# uhf_indication_v2.net
KiCad netlist of a schematic drawn in EAGLE
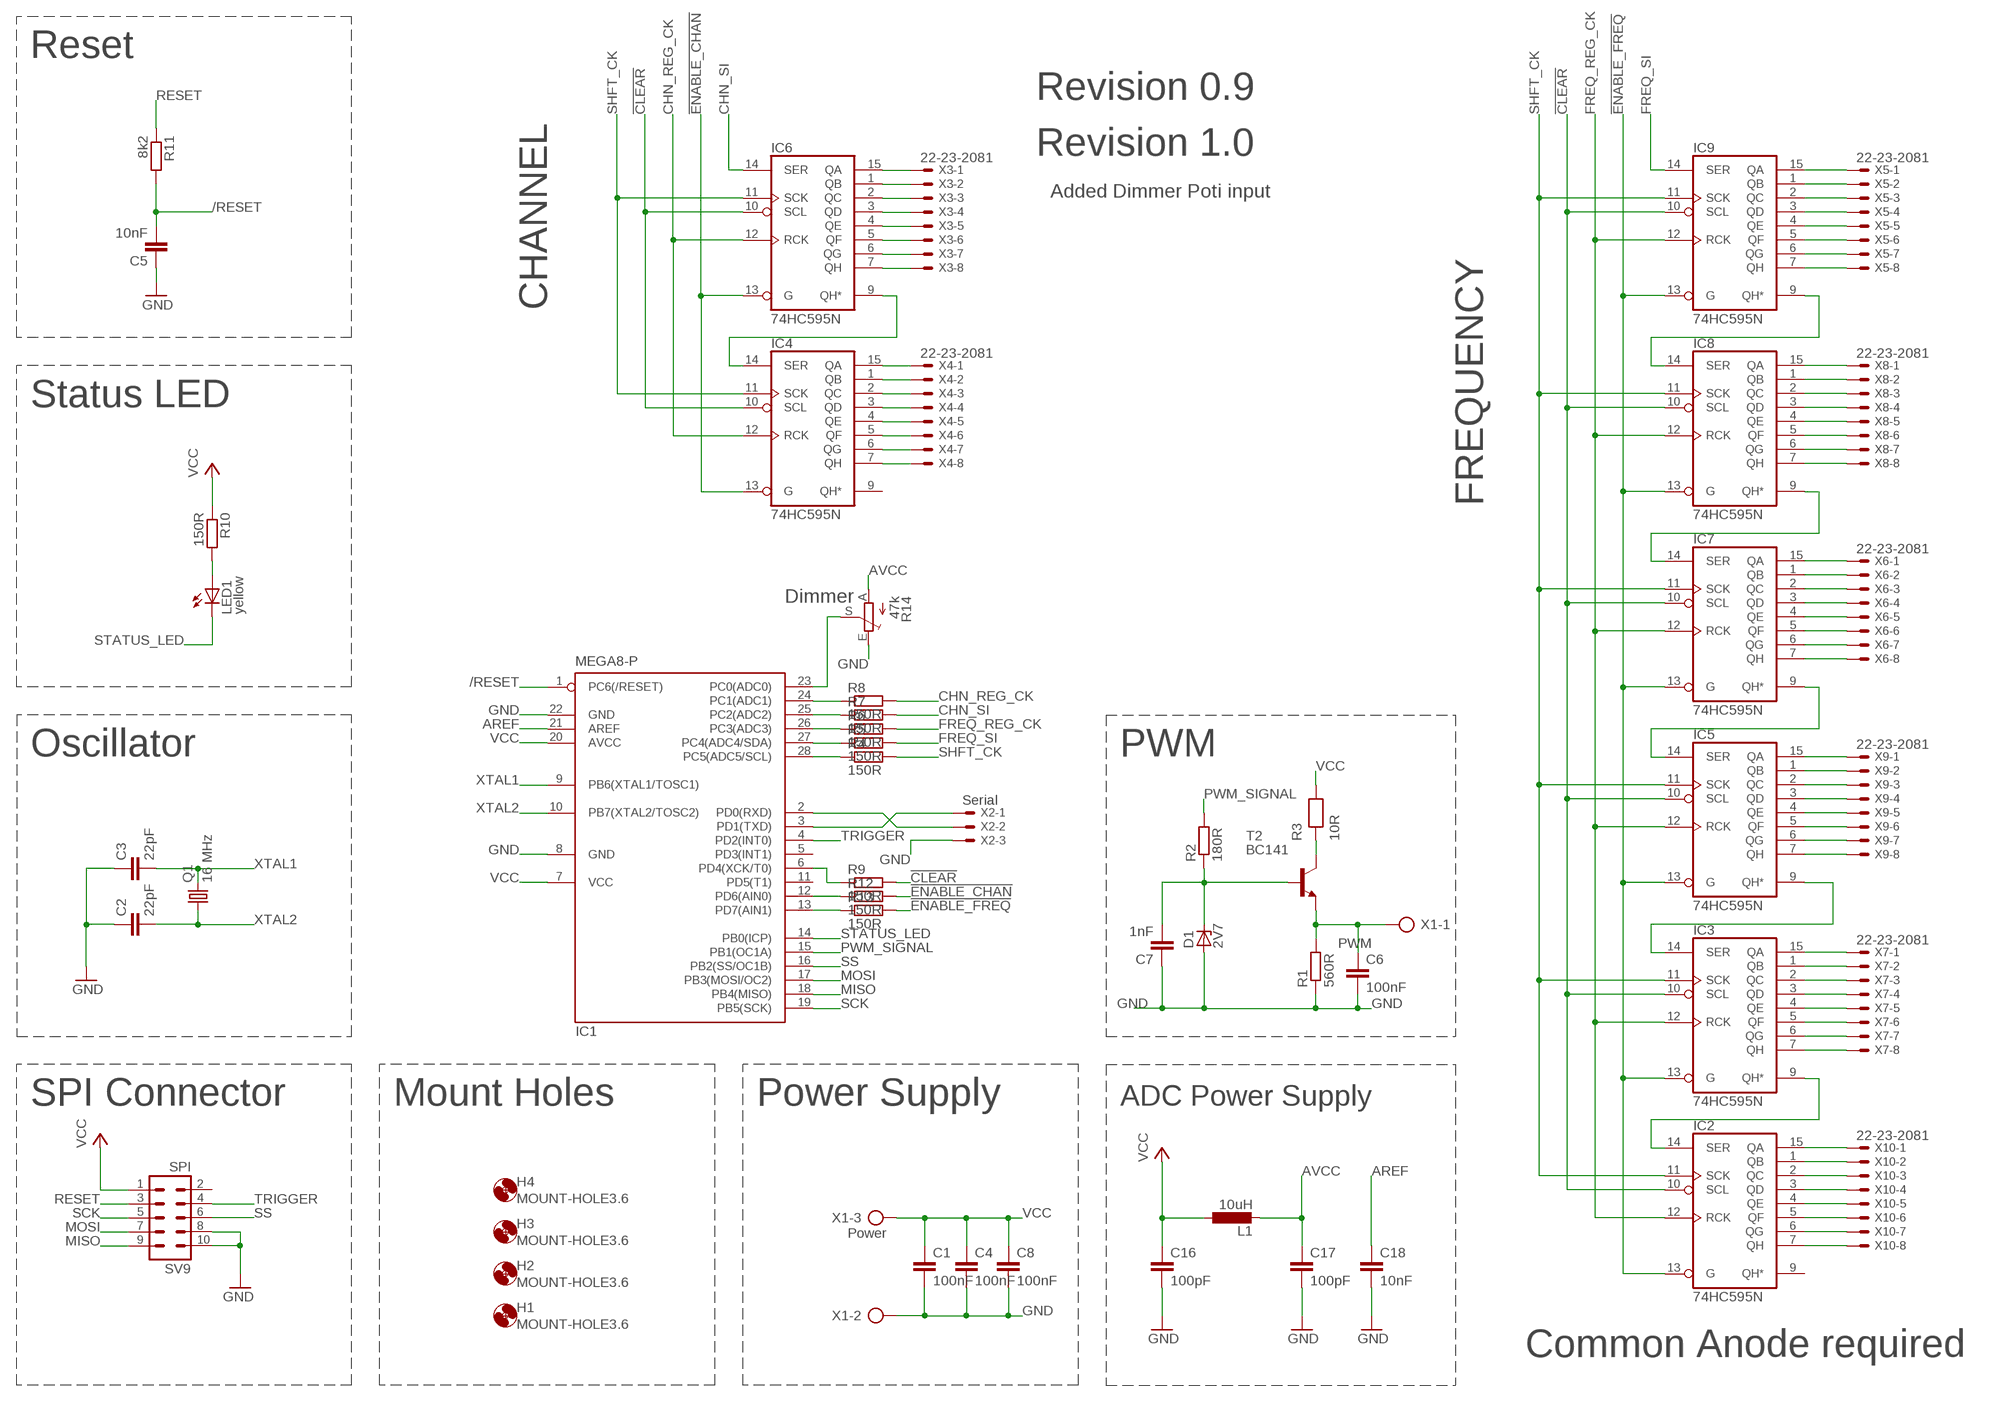
[diagram p0: schematic, sheet 1]

(export (version "E")
  (design (tool "Eeschema 10.0.6"))
  (components
    (comp (ref "C1")
      (value "100nF")
      (footprint "eagle-import:C050-024X044")
      (libsource (lib "eagle-import") (part "C-EU050-024X044"))
    )
    (comp (ref "C2")
      (value "22pF")
      (footprint "eagle-import:C025-025X050")
      (libsource (lib "eagle-import") (part "C-EU025-025X050"))
    )
    (comp (ref "C3")
      (value "22pF")
      (footprint "eagle-import:C025-025X050")
      (libsource (lib "eagle-import") (part "C-EU025-025X050"))
    )
    (comp (ref "C4")
      (value "100nF")
      (footprint "eagle-import:C050-024X044")
      (libsource (lib "eagle-import") (part "C-EU050-024X044"))
    )
    (comp (ref "C5")
      (value "10nF")
      (footprint "eagle-import:C025-025X050")
      (libsource (lib "eagle-import") (part "C-EU025-025X050"))
    )
    (comp (ref "C6")
      (value "100nF")
      (footprint "eagle-import:C050-024X044")
      (libsource (lib "eagle-import") (part "C-EU050-024X044"))
    )
    (comp (ref "C7")
      (value "1nF")
      (footprint "eagle-import:C025-025X050")
      (libsource (lib "eagle-import") (part "C-EU025-025X050"))
    )
    (comp (ref "C8")
      (value "100nF")
      (footprint "eagle-import:C050-024X044")
      (libsource (lib "eagle-import") (part "C-EU050-024X044"))
    )
    (comp (ref "C16")
      (value "100pF")
      (footprint "eagle-import:C025-025X050")
      (libsource (lib "eagle-import") (part "C-EU025-025X050"))
    )
    (comp (ref "C17")
      (value "100pF")
      (footprint "eagle-import:C025-025X050")
      (libsource (lib "eagle-import") (part "C-EU025-025X050"))
    )
    (comp (ref "C18")
      (value "10nF")
      (footprint "eagle-import:C025-025X050")
      (libsource (lib "eagle-import") (part "C-EU025-025X050"))
    )
    (comp (ref "D1")
      (value "2V7")
      (footprint "eagle-import:ZDIO-10")
      (libsource (lib "eagle-import") (part "ZENER-DIODEZD-10"))
    )
    (comp (ref "H1")
      (value "MOUNT-HOLE3.6")
      (footprint "eagle-import:3,6")
      (libsource (lib "eagle-import") (part "MOUNT-HOLE3.6"))
    )
    (comp (ref "H2")
      (value "MOUNT-HOLE3.6")
      (footprint "eagle-import:3,6")
      (libsource (lib "eagle-import") (part "MOUNT-HOLE3.6"))
    )
    (comp (ref "H3")
      (value "MOUNT-HOLE3.6")
      (footprint "eagle-import:3,6")
      (libsource (lib "eagle-import") (part "MOUNT-HOLE3.6"))
    )
    (comp (ref "H4")
      (value "MOUNT-HOLE3.6")
      (footprint "eagle-import:3,6")
      (libsource (lib "eagle-import") (part "MOUNT-HOLE3.6"))
    )
    (comp (ref "IC1")
      (value "MEGA8-P")
      (footprint "eagle-import:DIL28-3")
      (libsource (lib "eagle-import") (part "MEGA8-P"))
    )
    (comp (ref "IC2")
      (value "74HC595N")
      (footprint "eagle-import:DIL16")
      (libsource (lib "eagle-import") (part "74595NHC"))
    )
    (comp (ref "IC3")
      (value "74HC595N")
      (footprint "eagle-import:DIL16")
      (libsource (lib "eagle-import") (part "74595NHC"))
    )
    (comp (ref "IC4")
      (value "74HC595N")
      (footprint "eagle-import:DIL16")
      (libsource (lib "eagle-import") (part "74595NHC"))
    )
    (comp (ref "IC5")
      (value "74HC595N")
      (footprint "eagle-import:DIL16")
      (libsource (lib "eagle-import") (part "74595NHC"))
    )
    (comp (ref "IC6")
      (value "74HC595N")
      (footprint "eagle-import:DIL16")
      (libsource (lib "eagle-import") (part "74595NHC"))
    )
    (comp (ref "IC7")
      (value "74HC595N")
      (footprint "eagle-import:DIL16")
      (libsource (lib "eagle-import") (part "74595NHC"))
    )
    (comp (ref "IC8")
      (value "74HC595N")
      (footprint "eagle-import:DIL16")
      (libsource (lib "eagle-import") (part "74595NHC"))
    )
    (comp (ref "IC9")
      (value "74HC595N")
      (footprint "eagle-import:DIL16")
      (libsource (lib "eagle-import") (part "74595NHC"))
    )
    (comp (ref "L1")
      (value "10uH")
      (footprint "eagle-import:2200-15.24")
      (libsource (lib "eagle-import") (part "L-EU2200-15.24"))
    )
    (comp (ref "LED1")
      (value "yellow")
      (footprint "eagle-import:CHIPLED_1206")
      (libsource (lib "eagle-import") (part "LEDCHIPLED_1206"))
    )
    (comp (ref "Q1")
      (value "16 MHz")
      (footprint "eagle-import:HC18U-V")
      (libsource (lib "eagle-import") (part "CRYSTALHC18U-V"))
    )
    (comp (ref "R1")
      (value "560R")
      (footprint "eagle-import:0207_2V@1")
      (libsource (lib "eagle-import") (part "R-EU_0207/2V"))
    )
    (comp (ref "R2")
      (value "180R")
      (footprint "eagle-import:0207_2V@1")
      (libsource (lib "eagle-import") (part "R-EU_0207/2V"))
    )
    (comp (ref "R3")
      (value "10R")
      (footprint "eagle-import:208-08")
      (libsource (lib "eagle-import") (part "RESISTOR"))
    )
    (comp (ref "R4")
      (value "150R")
      (footprint "eagle-import:R0805")
      (libsource (lib "eagle-import") (part "R-EU_R0805"))
    )
    (comp (ref "R5")
      (value "150R")
      (footprint "eagle-import:R0805")
      (libsource (lib "eagle-import") (part "R-EU_R0805"))
    )
    (comp (ref "R6")
      (value "150R")
      (footprint "eagle-import:R0805")
      (libsource (lib "eagle-import") (part "R-EU_R0805"))
    )
    (comp (ref "R7")
      (value "150R")
      (footprint "eagle-import:R0805")
      (libsource (lib "eagle-import") (part "R-EU_R0805"))
    )
    (comp (ref "R8")
      (value "150R")
      (footprint "eagle-import:R0805")
      (libsource (lib "eagle-import") (part "R-EU_R0805"))
    )
    (comp (ref "R9")
      (value "150R")
      (footprint "eagle-import:R0805")
      (libsource (lib "eagle-import") (part "R-EU_R0805"))
    )
    (comp (ref "R10")
      (value "150R")
      (footprint "eagle-import:R0805")
      (libsource (lib "eagle-import") (part "R-EU_R0805"))
    )
    (comp (ref "R11")
      (value "8k2")
      (footprint "eagle-import:M0805")
      (libsource (lib "eagle-import") (part "R-EU_M0805"))
    )
    (comp (ref "R12")
      (value "150R")
      (footprint "eagle-import:R0805")
      (libsource (lib "eagle-import") (part "R-EU_R0805"))
    )
    (comp (ref "R13")
      (value "150R")
      (footprint "eagle-import:R0805")
      (libsource (lib "eagle-import") (part "R-EU_R0805"))
    )
    (comp (ref "R14")
      (value "47k")
      (footprint "eagle-import:B25V")
      (libsource (lib "eagle-import") (part "TRIM_EU-B25V"))
    )
    (comp (ref "SV9")
      (value "SPI")
      (footprint "eagle-import:ML10")
      (libsource (lib "eagle-import") (part "ML10"))
    )
    (comp (ref "T2")
      (value "BC141")
      (footprint "eagle-import:TO39")
      (libsource (lib "eagle-import") (part "-NPN-TO39-EBCBC141-16"))
    )
    (comp (ref "X1")
      (value "Power")
      (footprint "eagle-import:AK500_3")
      (libsource (lib "eagle-import") (part "AK500/3"))
    )
    (comp (ref "X2")
      (value "Serial")
      (footprint "eagle-import:22-23-2031")
      (libsource (lib "eagle-import") (part "22-23-2031"))
    )
    (comp (ref "X3")
      (value "22-23-2081")
      (footprint "eagle-import:22-23-2081")
      (libsource (lib "eagle-import") (part "22-23-2081"))
    )
    (comp (ref "X4")
      (value "22-23-2081")
      (footprint "eagle-import:22-23-2081")
      (libsource (lib "eagle-import") (part "22-23-2081"))
    )
    (comp (ref "X5")
      (value "22-23-2081")
      (footprint "eagle-import:22-23-2081")
      (libsource (lib "eagle-import") (part "22-23-2081"))
    )
    (comp (ref "X6")
      (value "22-23-2081")
      (footprint "eagle-import:22-23-2081")
      (libsource (lib "eagle-import") (part "22-23-2081"))
    )
    (comp (ref "X7")
      (value "22-23-2081")
      (footprint "eagle-import:22-23-2081")
      (libsource (lib "eagle-import") (part "22-23-2081"))
    )
    (comp (ref "X8")
      (value "22-23-2081")
      (footprint "eagle-import:22-23-2081")
      (libsource (lib "eagle-import") (part "22-23-2081"))
    )
    (comp (ref "X9")
      (value "22-23-2081")
      (footprint "eagle-import:22-23-2081")
      (libsource (lib "eagle-import") (part "22-23-2081"))
    )
    (comp (ref "X10")
      (value "22-23-2081")
      (footprint "eagle-import:22-23-2081")
      (libsource (lib "eagle-import") (part "22-23-2081"))
    )
  )
  (nets
    (net (code "1") (name "/AREF") (class "Default")
      (node (ref "C18") (pin "1") (pinfunction "1_1") (pintype "passive"))
      (node (ref "IC1") (pin "21") (pinfunction "AREF_21") (pintype "passive"))
    )
    (net (code "2") (name "/AVCC") (class "Default")
      (node (ref "C17") (pin "1") (pinfunction "1_1") (pintype "passive"))
      (node (ref "L1") (pin "2") (pinfunction "2_2") (pintype "passive"))
      (node (ref "R14") (pin "A") (pinfunction "A_A") (pintype "passive"))
    )
    (net (code "3") (name "/CHN_REG_CK") (class "Default")
      (node (ref "IC4") (pin "12") (pinfunction "RCK_12") (pintype "input"))
      (node (ref "IC6") (pin "12") (pinfunction "RCK_12") (pintype "input"))
      (node (ref "R8") (pin "2") (pinfunction "2_2") (pintype "passive"))
    )
    (net (code "4") (name "/CHN_SI") (class "Default")
      (node (ref "IC6") (pin "14") (pinfunction "SER_14") (pintype "input"))
      (node (ref "R7") (pin "2") (pinfunction "2_2") (pintype "passive"))
    )
    (net (code "5") (name "/FREQ_REG_CK") (class "Default")
      (node (ref "IC2") (pin "12") (pinfunction "RCK_12") (pintype "input"))
      (node (ref "IC3") (pin "12") (pinfunction "RCK_12") (pintype "input"))
      (node (ref "IC5") (pin "12") (pinfunction "RCK_12") (pintype "input"))
      (node (ref "IC7") (pin "12") (pinfunction "RCK_12") (pintype "input"))
      (node (ref "IC8") (pin "12") (pinfunction "RCK_12") (pintype "input"))
      (node (ref "IC9") (pin "12") (pinfunction "RCK_12") (pintype "input"))
      (node (ref "R6") (pin "2") (pinfunction "2_2") (pintype "passive"))
    )
    (net (code "6") (name "/FREQ_SI") (class "Default")
      (node (ref "IC9") (pin "14") (pinfunction "SER_14") (pintype "input"))
      (node (ref "R5") (pin "2") (pinfunction "2_2") (pintype "passive"))
    )
    (net (code "7") (name "/MISO") (class "Default")
      (node (ref "IC1") (pin "18") (pinfunction "PB4(MISO)_18") (pintype "bidirectional"))
      (node (ref "SV9") (pin "9") (pinfunction "9_9") (pintype "passive"))
    )
    (net (code "8") (name "/MOSI") (class "Default")
      (node (ref "IC1") (pin "17") (pinfunction "PB3(MOSI/OC2)_17") (pintype "bidirectional"))
      (node (ref "SV9") (pin "7") (pinfunction "7_7") (pintype "passive"))
    )
    (net (code "9") (name "/PWM") (class "Default")
      (node (ref "C6") (pin "1") (pinfunction "1_1") (pintype "passive"))
      (node (ref "R1") (pin "2") (pinfunction "2_2") (pintype "passive"))
      (node (ref "T2") (pin "1") (pinfunction "E_1") (pintype "passive"))
      (node (ref "X1") (pin "1") (pinfunction "KL_1") (pintype "passive"))
    )
    (net (code "10") (name "/PWM_SIGNAL") (class "Default")
      (node (ref "IC1") (pin "15") (pinfunction "PB1(OC1A)_15") (pintype "bidirectional"))
      (node (ref "R2") (pin "2") (pinfunction "2_2") (pintype "passive"))
    )
    (net (code "11") (name "/RESET") (class "Default")
      (node (ref "R11") (pin "1") (pinfunction "1_1") (pintype "passive"))
      (node (ref "SV9") (pin "3") (pinfunction "3_3") (pintype "passive"))
    )
    (net (code "12") (name "/SCK") (class "Default")
      (node (ref "IC1") (pin "19") (pinfunction "PB5(SCK)_19") (pintype "bidirectional"))
      (node (ref "SV9") (pin "5") (pinfunction "5_5") (pintype "passive"))
    )
    (net (code "13") (name "/SHFT_CK") (class "Default")
      (node (ref "IC2") (pin "11") (pinfunction "SCK_11") (pintype "input"))
      (node (ref "IC3") (pin "11") (pinfunction "SCK_11") (pintype "input"))
      (node (ref "IC4") (pin "11") (pinfunction "SCK_11") (pintype "input"))
      (node (ref "IC5") (pin "11") (pinfunction "SCK_11") (pintype "input"))
      (node (ref "IC6") (pin "11") (pinfunction "SCK_11") (pintype "input"))
      (node (ref "IC7") (pin "11") (pinfunction "SCK_11") (pintype "input"))
      (node (ref "IC8") (pin "11") (pinfunction "SCK_11") (pintype "input"))
      (node (ref "IC9") (pin "11") (pinfunction "SCK_11") (pintype "input"))
      (node (ref "R4") (pin "2") (pinfunction "2_2") (pintype "passive"))
    )
    (net (code "14") (name "/SS") (class "Default")
      (node (ref "IC1") (pin "16") (pinfunction "PB2(SS/OC1B)_16") (pintype "bidirectional"))
      (node (ref "SV9") (pin "6") (pinfunction "6_6") (pintype "passive"))
    )
    (net (code "15") (name "/STATUS_LED") (class "Default")
      (node (ref "IC1") (pin "14") (pinfunction "PB0(ICP)_14") (pintype "bidirectional"))
      (node (ref "LED1") (pin "C") (pinfunction "C_C") (pintype "passive"))
    )
    (net (code "16") (name "/TRIGGER") (class "Default")
      (node (ref "IC1") (pin "4") (pinfunction "PD2(INT0)_4") (pintype "bidirectional"))
      (node (ref "SV9") (pin "4") (pinfunction "4_4") (pintype "passive"))
    )
    (net (code "17") (name "/XTAL1") (class "Default")
      (node (ref "C3") (pin "2") (pinfunction "2_2") (pintype "passive"))
      (node (ref "IC1") (pin "9") (pinfunction "PB6(XTAL1/TOSC1)_9") (pintype "bidirectional"))
      (node (ref "Q1") (pin "2") (pinfunction "2_2") (pintype "passive"))
    )
    (net (code "18") (name "/XTAL2") (class "Default")
      (node (ref "C2") (pin "2") (pinfunction "2_2") (pintype "passive"))
      (node (ref "IC1") (pin "10") (pinfunction "PB7(XTAL2/TOSC2)_10") (pintype "bidirectional"))
      (node (ref "Q1") (pin "1") (pinfunction "1_1") (pintype "passive"))
    )
    (net (code "19") (name "/{slash}RESET") (class "Default")
      (node (ref "C5") (pin "2") (pinfunction "2_2") (pintype "passive"))
      (node (ref "IC1") (pin "1") (pinfunction "PC6(/RESET)_1") (pintype "bidirectional"))
      (node (ref "R11") (pin "2") (pinfunction "2_2") (pintype "passive"))
    )
    (net (code "20") (name "/~{CLEAR}") (class "Default")
      (node (ref "IC2") (pin "10") (pinfunction "SCL_10") (pintype "input"))
      (node (ref "IC3") (pin "10") (pinfunction "SCL_10") (pintype "input"))
      (node (ref "IC4") (pin "10") (pinfunction "SCL_10") (pintype "input"))
      (node (ref "IC5") (pin "10") (pinfunction "SCL_10") (pintype "input"))
      (node (ref "IC6") (pin "10") (pinfunction "SCL_10") (pintype "input"))
      (node (ref "IC7") (pin "10") (pinfunction "SCL_10") (pintype "input"))
      (node (ref "IC8") (pin "10") (pinfunction "SCL_10") (pintype "input"))
      (node (ref "IC9") (pin "10") (pinfunction "SCL_10") (pintype "input"))
      (node (ref "R9") (pin "2") (pinfunction "2_2") (pintype "passive"))
    )
    (net (code "21") (name "/~{ENABLE_CHAN}") (class "Default")
      (node (ref "IC4") (pin "13") (pinfunction "G_13") (pintype "input"))
      (node (ref "IC6") (pin "13") (pinfunction "G_13") (pintype "input"))
      (node (ref "R12") (pin "2") (pinfunction "2_2") (pintype "passive"))
    )
    (net (code "22") (name "/~{ENABLE_FREQ}") (class "Default")
      (node (ref "IC2") (pin "13") (pinfunction "G_13") (pintype "input"))
      (node (ref "IC3") (pin "13") (pinfunction "G_13") (pintype "input"))
      (node (ref "IC5") (pin "13") (pinfunction "G_13") (pintype "input"))
      (node (ref "IC7") (pin "13") (pinfunction "G_13") (pintype "input"))
      (node (ref "IC8") (pin "13") (pinfunction "G_13") (pintype "input"))
      (node (ref "IC9") (pin "13") (pinfunction "G_13") (pintype "input"))
      (node (ref "R13") (pin "2") (pinfunction "2_2") (pintype "passive"))
    )
    (net (code "23") (name "GND") (class "Default")
      (node (ref "C1") (pin "2") (pinfunction "2_2") (pintype "passive"))
      (node (ref "C16") (pin "2") (pinfunction "2_2") (pintype "passive"))
      (node (ref "C17") (pin "2") (pinfunction "2_2") (pintype "passive"))
      (node (ref "C18") (pin "2") (pinfunction "2_2") (pintype "passive"))
      (node (ref "C2") (pin "1") (pinfunction "1_1") (pintype "passive"))
      (node (ref "C3") (pin "1") (pinfunction "1_1") (pintype "passive"))
      (node (ref "C4") (pin "2") (pinfunction "2_2") (pintype "passive"))
      (node (ref "C5") (pin "1") (pinfunction "1_1") (pintype "passive"))
      (node (ref "C6") (pin "2") (pinfunction "2_2") (pintype "passive"))
      (node (ref "C7") (pin "1") (pinfunction "1_1") (pintype "passive"))
      (node (ref "C8") (pin "2") (pinfunction "2_2") (pintype "passive"))
      (node (ref "D1") (pin "A") (pinfunction "A_A") (pintype "passive"))
      (node (ref "IC1") (pin "22") (pinfunction "GND_22") (pintype "power_in"))
      (node (ref "IC1") (pin "8") (pinfunction "GND_8") (pintype "power_in"))
      (node (ref "R1") (pin "1") (pinfunction "1_1") (pintype "passive"))
      (node (ref "R14") (pin "E") (pinfunction "E_E") (pintype "passive"))
      (node (ref "SV9") (pin "10") (pinfunction "10_10") (pintype "passive"))
      (node (ref "SV9") (pin "8") (pinfunction "8_8") (pintype "passive"))
      (node (ref "X1") (pin "2") (pinfunction "KL_2") (pintype "passive"))
      (node (ref "X2") (pin "3") (pinfunction "S_3") (pintype "passive"))
    )
    (net (code "24") (name "Net-(IC1-PC0(ADC0))") (class "Default")
      (node (ref "IC1") (pin "23") (pinfunction "PC0(ADC0)_23") (pintype "bidirectional"))
      (node (ref "R14") (pin "S") (pinfunction "S_S") (pintype "passive"))
    )
    (net (code "25") (name "Net-(IC1-PC1(ADC1))") (class "Default")
      (node (ref "IC1") (pin "24") (pinfunction "PC1(ADC1)_24") (pintype "bidirectional"))
      (node (ref "R8") (pin "1") (pinfunction "1_1") (pintype "passive"))
    )
    (net (code "26") (name "Net-(IC1-PC2(ADC2))") (class "Default")
      (node (ref "IC1") (pin "25") (pinfunction "PC2(ADC2)_25") (pintype "bidirectional"))
      (node (ref "R7") (pin "1") (pinfunction "1_1") (pintype "passive"))
    )
    (net (code "27") (name "Net-(IC1-PC3(ADC3))") (class "Default")
      (node (ref "IC1") (pin "26") (pinfunction "PC3(ADC3)_26") (pintype "bidirectional"))
      (node (ref "R6") (pin "1") (pinfunction "1_1") (pintype "passive"))
    )
    (net (code "28") (name "Net-(IC1-PC4(ADC4{slash}SDA))") (class "Default")
      (node (ref "IC1") (pin "27") (pinfunction "PC4(ADC4/SDA)_27") (pintype "bidirectional"))
      (node (ref "R5") (pin "1") (pinfunction "1_1") (pintype "passive"))
    )
    (net (code "29") (name "Net-(IC1-PC5(ADC5{slash}SCL))") (class "Default")
      (node (ref "IC1") (pin "28") (pinfunction "PC5(ADC5/SCL)_28") (pintype "bidirectional"))
      (node (ref "R4") (pin "1") (pinfunction "1_1") (pintype "passive"))
    )
    (net (code "30") (name "Net-(IC1-PD0(RXD))") (class "Default")
      (node (ref "IC1") (pin "2") (pinfunction "PD0(RXD)_2") (pintype "bidirectional"))
      (node (ref "X2") (pin "2") (pinfunction "S_2") (pintype "passive"))
    )
    (net (code "31") (name "Net-(IC1-PD1(TXD))") (class "Default")
      (node (ref "IC1") (pin "3") (pinfunction "PD1(TXD)_3") (pintype "bidirectional"))
      (node (ref "X2") (pin "1") (pinfunction "S_1") (pintype "passive"))
    )
    (net (code "32") (name "Net-(IC1-PD4(XCK{slash}T0))") (class "Default")
      (node (ref "IC1") (pin "6") (pinfunction "PD4(XCK/T0)_6") (pintype "bidirectional"))
      (node (ref "R9") (pin "1") (pinfunction "1_1") (pintype "passive"))
    )
    (net (code "33") (name "Net-(IC1-PD6(AIN0))") (class "Default")
      (node (ref "IC1") (pin "12") (pinfunction "PD6(AIN0)_12") (pintype "bidirectional"))
      (node (ref "R12") (pin "1") (pinfunction "1_1") (pintype "passive"))
    )
    (net (code "34") (name "Net-(IC1-PD7(AIN1))") (class "Default")
      (node (ref "IC1") (pin "13") (pinfunction "PD7(AIN1)_13") (pintype "bidirectional"))
      (node (ref "R13") (pin "1") (pinfunction "1_1") (pintype "passive"))
    )
    (net (code "35") (name "Net-(IC2A-QA)") (class "Default")
      (node (ref "IC2") (pin "15") (pinfunction "QA_15") (pintype "tri_state"))
      (node (ref "X10") (pin "1") (pinfunction "S_1") (pintype "passive"))
    )
    (net (code "36") (name "Net-(IC2A-QB)") (class "Default")
      (node (ref "IC2") (pin "1") (pinfunction "QB_1") (pintype "tri_state"))
      (node (ref "X10") (pin "2") (pinfunction "S_2") (pintype "passive"))
    )
    (net (code "37") (name "Net-(IC2A-QC)") (class "Default")
      (node (ref "IC2") (pin "2") (pinfunction "QC_2") (pintype "tri_state"))
      (node (ref "X10") (pin "3") (pinfunction "S_3") (pintype "passive"))
    )
    (net (code "38") (name "Net-(IC2A-QD)") (class "Default")
      (node (ref "IC2") (pin "3") (pinfunction "QD_3") (pintype "tri_state"))
      (node (ref "X10") (pin "4") (pinfunction "S_4") (pintype "passive"))
    )
    (net (code "39") (name "Net-(IC2A-QE)") (class "Default")
      (node (ref "IC2") (pin "4") (pinfunction "QE_4") (pintype "tri_state"))
      (node (ref "X10") (pin "5") (pinfunction "S_5") (pintype "passive"))
    )
    (net (code "40") (name "Net-(IC2A-QF)") (class "Default")
      (node (ref "IC2") (pin "5") (pinfunction "QF_5") (pintype "tri_state"))
      (node (ref "X10") (pin "6") (pinfunction "S_6") (pintype "passive"))
    )
    (net (code "41") (name "Net-(IC2A-QG)") (class "Default")
      (node (ref "IC2") (pin "6") (pinfunction "QG_6") (pintype "tri_state"))
      (node (ref "X10") (pin "7") (pinfunction "S_7") (pintype "passive"))
    )
    (net (code "42") (name "Net-(IC2A-QH)") (class "Default")
      (node (ref "IC2") (pin "7") (pinfunction "QH_7") (pintype "tri_state"))
      (node (ref "X10") (pin "8") (pinfunction "S_8") (pintype "passive"))
    )
    (net (code "43") (name "Net-(IC2A-SER)") (class "Default")
      (node (ref "IC2") (pin "14") (pinfunction "SER_14") (pintype "input"))
      (node (ref "IC3") (pin "9") (pinfunction "QH*_9") (pintype "tri_state"))
    )
    (net (code "44") (name "Net-(IC3A-QA)") (class "Default")
      (node (ref "IC3") (pin "15") (pinfunction "QA_15") (pintype "tri_state"))
      (node (ref "X7") (pin "1") (pinfunction "S_1") (pintype "passive"))
    )
    (net (code "45") (name "Net-(IC3A-QB)") (class "Default")
      (node (ref "IC3") (pin "1") (pinfunction "QB_1") (pintype "tri_state"))
      (node (ref "X7") (pin "2") (pinfunction "S_2") (pintype "passive"))
    )
    (net (code "46") (name "Net-(IC3A-QC)") (class "Default")
      (node (ref "IC3") (pin "2") (pinfunction "QC_2") (pintype "tri_state"))
      (node (ref "X7") (pin "3") (pinfunction "S_3") (pintype "passive"))
    )
    (net (code "47") (name "Net-(IC3A-QD)") (class "Default")
      (node (ref "IC3") (pin "3") (pinfunction "QD_3") (pintype "tri_state"))
      (node (ref "X7") (pin "4") (pinfunction "S_4") (pintype "passive"))
    )
    (net (code "48") (name "Net-(IC3A-QE)") (class "Default")
      (node (ref "IC3") (pin "4") (pinfunction "QE_4") (pintype "tri_state"))
      (node (ref "X7") (pin "5") (pinfunction "S_5") (pintype "passive"))
    )
    (net (code "49") (name "Net-(IC3A-QF)") (class "Default")
      (node (ref "IC3") (pin "5") (pinfunction "QF_5") (pintype "tri_state"))
      (node (ref "X7") (pin "6") (pinfunction "S_6") (pintype "passive"))
    )
    (net (code "50") (name "Net-(IC3A-QG)") (class "Default")
      (node (ref "IC3") (pin "6") (pinfunction "QG_6") (pintype "tri_state"))
      (node (ref "X7") (pin "7") (pinfunction "S_7") (pintype "passive"))
    )
    (net (code "51") (name "Net-(IC3A-QH)") (class "Default")
      (node (ref "IC3") (pin "7") (pinfunction "QH_7") (pintype "tri_state"))
      (node (ref "X7") (pin "8") (pinfunction "S_8") (pintype "passive"))
    )
    (net (code "52") (name "Net-(IC3A-SER)") (class "Default")
      (node (ref "IC3") (pin "14") (pinfunction "SER_14") (pintype "input"))
      (node (ref "IC5") (pin "9") (pinfunction "QH*_9") (pintype "tri_state"))
    )
    (net (code "53") (name "Net-(IC4A-QA)") (class "Default")
      (node (ref "IC4") (pin "15") (pinfunction "QA_15") (pintype "tri_state"))
      (node (ref "X4") (pin "1") (pinfunction "S_1") (pintype "passive"))
    )
    (net (code "54") (name "Net-(IC4A-QB)") (class "Default")
      (node (ref "IC4") (pin "1") (pinfunction "QB_1") (pintype "tri_state"))
      (node (ref "X4") (pin "2") (pinfunction "S_2") (pintype "passive"))
    )
    (net (code "55") (name "Net-(IC4A-QC)") (class "Default")
      (node (ref "IC4") (pin "2") (pinfunction "QC_2") (pintype "tri_state"))
      (node (ref "X4") (pin "3") (pinfunction "S_3") (pintype "passive"))
    )
    (net (code "56") (name "Net-(IC4A-QD)") (class "Default")
      (node (ref "IC4") (pin "3") (pinfunction "QD_3") (pintype "tri_state"))
      (node (ref "X4") (pin "4") (pinfunction "S_4") (pintype "passive"))
    )
    (net (code "57") (name "Net-(IC4A-QE)") (class "Default")
      (node (ref "IC4") (pin "4") (pinfunction "QE_4") (pintype "tri_state"))
      (node (ref "X4") (pin "5") (pinfunction "S_5") (pintype "passive"))
    )
    (net (code "58") (name "Net-(IC4A-QF)") (class "Default")
      (node (ref "IC4") (pin "5") (pinfunction "QF_5") (pintype "tri_state"))
      (node (ref "X4") (pin "6") (pinfunction "S_6") (pintype "passive"))
    )
    (net (code "59") (name "Net-(IC4A-QG)") (class "Default")
      (node (ref "IC4") (pin "6") (pinfunction "QG_6") (pintype "tri_state"))
      (node (ref "X4") (pin "7") (pinfunction "S_7") (pintype "passive"))
    )
    (net (code "60") (name "Net-(IC4A-QH)") (class "Default")
      (node (ref "IC4") (pin "7") (pinfunction "QH_7") (pintype "tri_state"))
      (node (ref "X4") (pin "8") (pinfunction "S_8") (pintype "passive"))
    )
    (net (code "61") (name "Net-(IC4A-SER)") (class "Default")
      (node (ref "IC4") (pin "14") (pinfunction "SER_14") (pintype "input"))
      (node (ref "IC6") (pin "9") (pinfunction "QH*_9") (pintype "tri_state"))
    )
    (net (code "62") (name "Net-(IC5A-QA)") (class "Default")
      (node (ref "IC5") (pin "15") (pinfunction "QA_15") (pintype "tri_state"))
      (node (ref "X9") (pin "1") (pinfunction "S_1") (pintype "passive"))
    )
    (net (code "63") (name "Net-(IC5A-QB)") (class "Default")
      (node (ref "IC5") (pin "1") (pinfunction "QB_1") (pintype "tri_state"))
      (node (ref "X9") (pin "2") (pinfunction "S_2") (pintype "passive"))
    )
    (net (code "64") (name "Net-(IC5A-QC)") (class "Default")
      (node (ref "IC5") (pin "2") (pinfunction "QC_2") (pintype "tri_state"))
      (node (ref "X9") (pin "3") (pinfunction "S_3") (pintype "passive"))
    )
    (net (code "65") (name "Net-(IC5A-QD)") (class "Default")
      (node (ref "IC5") (pin "3") (pinfunction "QD_3") (pintype "tri_state"))
      (node (ref "X9") (pin "4") (pinfunction "S_4") (pintype "passive"))
    )
    (net (code "66") (name "Net-(IC5A-QE)") (class "Default")
      (node (ref "IC5") (pin "4") (pinfunction "QE_4") (pintype "tri_state"))
      (node (ref "X9") (pin "5") (pinfunction "S_5") (pintype "passive"))
    )
    (net (code "67") (name "Net-(IC5A-QF)") (class "Default")
      (node (ref "IC5") (pin "5") (pinfunction "QF_5") (pintype "tri_state"))
      (node (ref "X9") (pin "6") (pinfunction "S_6") (pintype "passive"))
    )
    (net (code "68") (name "Net-(IC5A-QG)") (class "Default")
      (node (ref "IC5") (pin "6") (pinfunction "QG_6") (pintype "tri_state"))
      (node (ref "X9") (pin "7") (pinfunction "S_7") (pintype "passive"))
    )
    (net (code "69") (name "Net-(IC5A-QH)") (class "Default")
      (node (ref "IC5") (pin "7") (pinfunction "QH_7") (pintype "tri_state"))
      (node (ref "X9") (pin "8") (pinfunction "S_8") (pintype "passive"))
    )
    (net (code "70") (name "Net-(IC5A-SER)") (class "Default")
      (node (ref "IC5") (pin "14") (pinfunction "SER_14") (pintype "input"))
      (node (ref "IC7") (pin "9") (pinfunction "QH*_9") (pintype "tri_state"))
    )
    (net (code "71") (name "Net-(IC6A-QA)") (class "Default")
      (node (ref "IC6") (pin "15") (pinfunction "QA_15") (pintype "tri_state"))
      (node (ref "X3") (pin "1") (pinfunction "S_1") (pintype "passive"))
    )
    (net (code "72") (name "Net-(IC6A-QB)") (class "Default")
      (node (ref "IC6") (pin "1") (pinfunction "QB_1") (pintype "tri_state"))
      (node (ref "X3") (pin "2") (pinfunction "S_2") (pintype "passive"))
    )
    (net (code "73") (name "Net-(IC6A-QC)") (class "Default")
      (node (ref "IC6") (pin "2") (pinfunction "QC_2") (pintype "tri_state"))
      (node (ref "X3") (pin "3") (pinfunction "S_3") (pintype "passive"))
    )
    (net (code "74") (name "Net-(IC6A-QD)") (class "Default")
      (node (ref "IC6") (pin "3") (pinfunction "QD_3") (pintype "tri_state"))
      (node (ref "X3") (pin "4") (pinfunction "S_4") (pintype "passive"))
    )
    (net (code "75") (name "Net-(IC6A-QE)") (class "Default")
      (node (ref "IC6") (pin "4") (pinfunction "QE_4") (pintype "tri_state"))
      (node (ref "X3") (pin "5") (pinfunction "S_5") (pintype "passive"))
    )
    (net (code "76") (name "Net-(IC6A-QF)") (class "Default")
      (node (ref "IC6") (pin "5") (pinfunction "QF_5") (pintype "tri_state"))
      (node (ref "X3") (pin "6") (pinfunction "S_6") (pintype "passive"))
    )
    (net (code "77") (name "Net-(IC6A-QG)") (class "Default")
      (node (ref "IC6") (pin "6") (pinfunction "QG_6") (pintype "tri_state"))
      (node (ref "X3") (pin "7") (pinfunction "S_7") (pintype "passive"))
    )
    (net (code "78") (name "Net-(IC6A-QH)") (class "Default")
      (node (ref "IC6") (pin "7") (pinfunction "QH_7") (pintype "tri_state"))
      (node (ref "X3") (pin "8") (pinfunction "S_8") (pintype "passive"))
    )
    (net (code "79") (name "Net-(IC7A-QA)") (class "Default")
      (node (ref "IC7") (pin "15") (pinfunction "QA_15") (pintype "tri_state"))
      (node (ref "X6") (pin "1") (pinfunction "S_1") (pintype "passive"))
    )
    (net (code "80") (name "Net-(IC7A-QB)") (class "Default")
      (node (ref "IC7") (pin "1") (pinfunction "QB_1") (pintype "tri_state"))
      (node (ref "X6") (pin "2") (pinfunction "S_2") (pintype "passive"))
    )
    (net (code "81") (name "Net-(IC7A-QC)") (class "Default")
      (node (ref "IC7") (pin "2") (pinfunction "QC_2") (pintype "tri_state"))
      (node (ref "X6") (pin "3") (pinfunction "S_3") (pintype "passive"))
    )
    (net (code "82") (name "Net-(IC7A-QD)") (class "Default")
      (node (ref "IC7") (pin "3") (pinfunction "QD_3") (pintype "tri_state"))
      (node (ref "X6") (pin "4") (pinfunction "S_4") (pintype "passive"))
    )
    (net (code "83") (name "Net-(IC7A-QE)") (class "Default")
      (node (ref "IC7") (pin "4") (pinfunction "QE_4") (pintype "tri_state"))
      (node (ref "X6") (pin "5") (pinfunction "S_5") (pintype "passive"))
    )
    (net (code "84") (name "Net-(IC7A-QF)") (class "Default")
      (node (ref "IC7") (pin "5") (pinfunction "QF_5") (pintype "tri_state"))
      (node (ref "X6") (pin "6") (pinfunction "S_6") (pintype "passive"))
    )
    (net (code "85") (name "Net-(IC7A-QG)") (class "Default")
      (node (ref "IC7") (pin "6") (pinfunction "QG_6") (pintype "tri_state"))
      (node (ref "X6") (pin "7") (pinfunction "S_7") (pintype "passive"))
    )
    (net (code "86") (name "Net-(IC7A-QH)") (class "Default")
      (node (ref "IC7") (pin "7") (pinfunction "QH_7") (pintype "tri_state"))
      (node (ref "X6") (pin "8") (pinfunction "S_8") (pintype "passive"))
    )
    (net (code "87") (name "Net-(IC7A-SER)") (class "Default")
      (node (ref "IC7") (pin "14") (pinfunction "SER_14") (pintype "input"))
      (node (ref "IC8") (pin "9") (pinfunction "QH*_9") (pintype "tri_state"))
    )
    (net (code "88") (name "Net-(IC8A-QA)") (class "Default")
      (node (ref "IC8") (pin "15") (pinfunction "QA_15") (pintype "tri_state"))
      (node (ref "X8") (pin "1") (pinfunction "S_1") (pintype "passive"))
    )
    (net (code "89") (name "Net-(IC8A-QB)") (class "Default")
      (node (ref "IC8") (pin "1") (pinfunction "QB_1") (pintype "tri_state"))
      (node (ref "X8") (pin "2") (pinfunction "S_2") (pintype "passive"))
    )
    (net (code "90") (name "Net-(IC8A-QC)") (class "Default")
      (node (ref "IC8") (pin "2") (pinfunction "QC_2") (pintype "tri_state"))
      (node (ref "X8") (pin "3") (pinfunction "S_3") (pintype "passive"))
    )
    (net (code "91") (name "Net-(IC8A-QD)") (class "Default")
      (node (ref "IC8") (pin "3") (pinfunction "QD_3") (pintype "tri_state"))
      (node (ref "X8") (pin "4") (pinfunction "S_4") (pintype "passive"))
    )
    (net (code "92") (name "Net-(IC8A-QE)") (class "Default")
      (node (ref "IC8") (pin "4") (pinfunction "QE_4") (pintype "tri_state"))
      (node (ref "X8") (pin "5") (pinfunction "S_5") (pintype "passive"))
    )
    (net (code "93") (name "Net-(IC8A-QF)") (class "Default")
      (node (ref "IC8") (pin "5") (pinfunction "QF_5") (pintype "tri_state"))
      (node (ref "X8") (pin "6") (pinfunction "S_6") (pintype "passive"))
    )
    (net (code "94") (name "Net-(IC8A-QG)") (class "Default")
      (node (ref "IC8") (pin "6") (pinfunction "QG_6") (pintype "tri_state"))
      (node (ref "X8") (pin "7") (pinfunction "S_7") (pintype "passive"))
    )
    (net (code "95") (name "Net-(IC8A-QH)") (class "Default")
      (node (ref "IC8") (pin "7") (pinfunction "QH_7") (pintype "tri_state"))
      (node (ref "X8") (pin "8") (pinfunction "S_8") (pintype "passive"))
    )
    (net (code "96") (name "Net-(IC8A-SER)") (class "Default")
      (node (ref "IC8") (pin "14") (pinfunction "SER_14") (pintype "input"))
      (node (ref "IC9") (pin "9") (pinfunction "QH*_9") (pintype "tri_state"))
    )
    (net (code "97") (name "Net-(IC9A-QA)") (class "Default")
      (node (ref "IC9") (pin "15") (pinfunction "QA_15") (pintype "tri_state"))
      (node (ref "X5") (pin "1") (pinfunction "S_1") (pintype "passive"))
    )
    (net (code "98") (name "Net-(IC9A-QB)") (class "Default")
      (node (ref "IC9") (pin "1") (pinfunction "QB_1") (pintype "tri_state"))
      (node (ref "X5") (pin "2") (pinfunction "S_2") (pintype "passive"))
    )
    (net (code "99") (name "Net-(IC9A-QC)") (class "Default")
      (node (ref "IC9") (pin "2") (pinfunction "QC_2") (pintype "tri_state"))
      (node (ref "X5") (pin "3") (pinfunction "S_3") (pintype "passive"))
    )
    (net (code "100") (name "Net-(IC9A-QD)") (class "Default")
      (node (ref "IC9") (pin "3") (pinfunction "QD_3") (pintype "tri_state"))
      (node (ref "X5") (pin "4") (pinfunction "S_4") (pintype "passive"))
    )
    (net (code "101") (name "Net-(IC9A-QE)") (class "Default")
      (node (ref "IC9") (pin "4") (pinfunction "QE_4") (pintype "tri_state"))
      (node (ref "X5") (pin "5") (pinfunction "S_5") (pintype "passive"))
    )
    (net (code "102") (name "Net-(IC9A-QF)") (class "Default")
      (node (ref "IC9") (pin "5") (pinfunction "QF_5") (pintype "tri_state"))
      (node (ref "X5") (pin "6") (pinfunction "S_6") (pintype "passive"))
    )
    (net (code "103") (name "Net-(IC9A-QG)") (class "Default")
      (node (ref "IC9") (pin "6") (pinfunction "QG_6") (pintype "tri_state"))
      (node (ref "X5") (pin "7") (pinfunction "S_7") (pintype "passive"))
    )
    (net (code "104") (name "Net-(IC9A-QH)") (class "Default")
      (node (ref "IC9") (pin "7") (pinfunction "QH_7") (pintype "tri_state"))
      (node (ref "X5") (pin "8") (pinfunction "S_8") (pintype "passive"))
    )
    (net (code "105") (name "Net-(LED1-PadA)") (class "Default")
      (node (ref "LED1") (pin "A") (pinfunction "A_A") (pintype "passive"))
      (node (ref "R10") (pin "2") (pinfunction "2_2") (pintype "passive"))
    )
    (net (code "106") (name "Net-(T2-B)") (class "Default")
      (node (ref "C7") (pin "2") (pinfunction "2_2") (pintype "passive"))
      (node (ref "D1") (pin "C") (pinfunction "C_C") (pintype "passive"))
      (node (ref "R2") (pin "1") (pinfunction "1_1") (pintype "passive"))
      (node (ref "T2") (pin "2") (pinfunction "B_2") (pintype "passive"))
    )
    (net (code "107") (name "Net-(T2-C)") (class "Default")
      (node (ref "R3") (pin "P$2") (pinfunction "P$2_P$2") (pintype "passive"))
      (node (ref "T2") (pin "3") (pinfunction "C_3") (pintype "passive"))
    )
    (net (code "108") (name "VCC") (class "Default")
      (node (ref "C1") (pin "1") (pinfunction "1_1") (pintype "passive"))
      (node (ref "C16") (pin "1") (pinfunction "1_1") (pintype "passive"))
      (node (ref "C4") (pin "1") (pinfunction "1_1") (pintype "passive"))
      (node (ref "C8") (pin "1") (pinfunction "1_1") (pintype "passive"))
      (node (ref "IC1") (pin "20") (pinfunction "AVCC_20") (pintype "power_in"))
      (node (ref "IC1") (pin "7") (pinfunction "VCC_7") (pintype "power_in"))
      (node (ref "L1") (pin "1") (pinfunction "1_1") (pintype "passive"))
      (node (ref "R10") (pin "1") (pinfunction "1_1") (pintype "passive"))
      (node (ref "R3") (pin "P$1") (pinfunction "P$1_P$1") (pintype "passive"))
      (node (ref "SV9") (pin "1") (pinfunction "1_1") (pintype "passive"))
      (node (ref "X1") (pin "3") (pinfunction "KL_3") (pintype "passive"))
    )
    (net (code "109") (name "unconnected-(IC1-PD3(INT1)-Pad5)") (class "Default")
      (node (ref "IC1") (pin "5") (pinfunction "PD3(INT1)_5") (pintype "bidirectional"))
    )
    (net (code "110") (name "unconnected-(IC1-PD5(T1)-Pad11)") (class "Default")
      (node (ref "IC1") (pin "11") (pinfunction "PD5(T1)_11") (pintype "bidirectional"))
    )
    (net (code "111") (name "unconnected-(IC2A-QH*-Pad9)") (class "Default")
      (node (ref "IC2") (pin "9") (pinfunction "QH*_9") (pintype "tri_state"))
    )
    (net (code "112") (name "unconnected-(IC4A-QH*-Pad9)") (class "Default")
      (node (ref "IC4") (pin "9") (pinfunction "QH*_9") (pintype "tri_state"))
    )
    (net (code "113") (name "unconnected-(SV9-Pad2)") (class "Default")
      (node (ref "SV9") (pin "2") (pinfunction "2_2") (pintype "passive"))
    )
  )
)
